# main.net
KiCad netlist of a schematic drawn in EAGLE
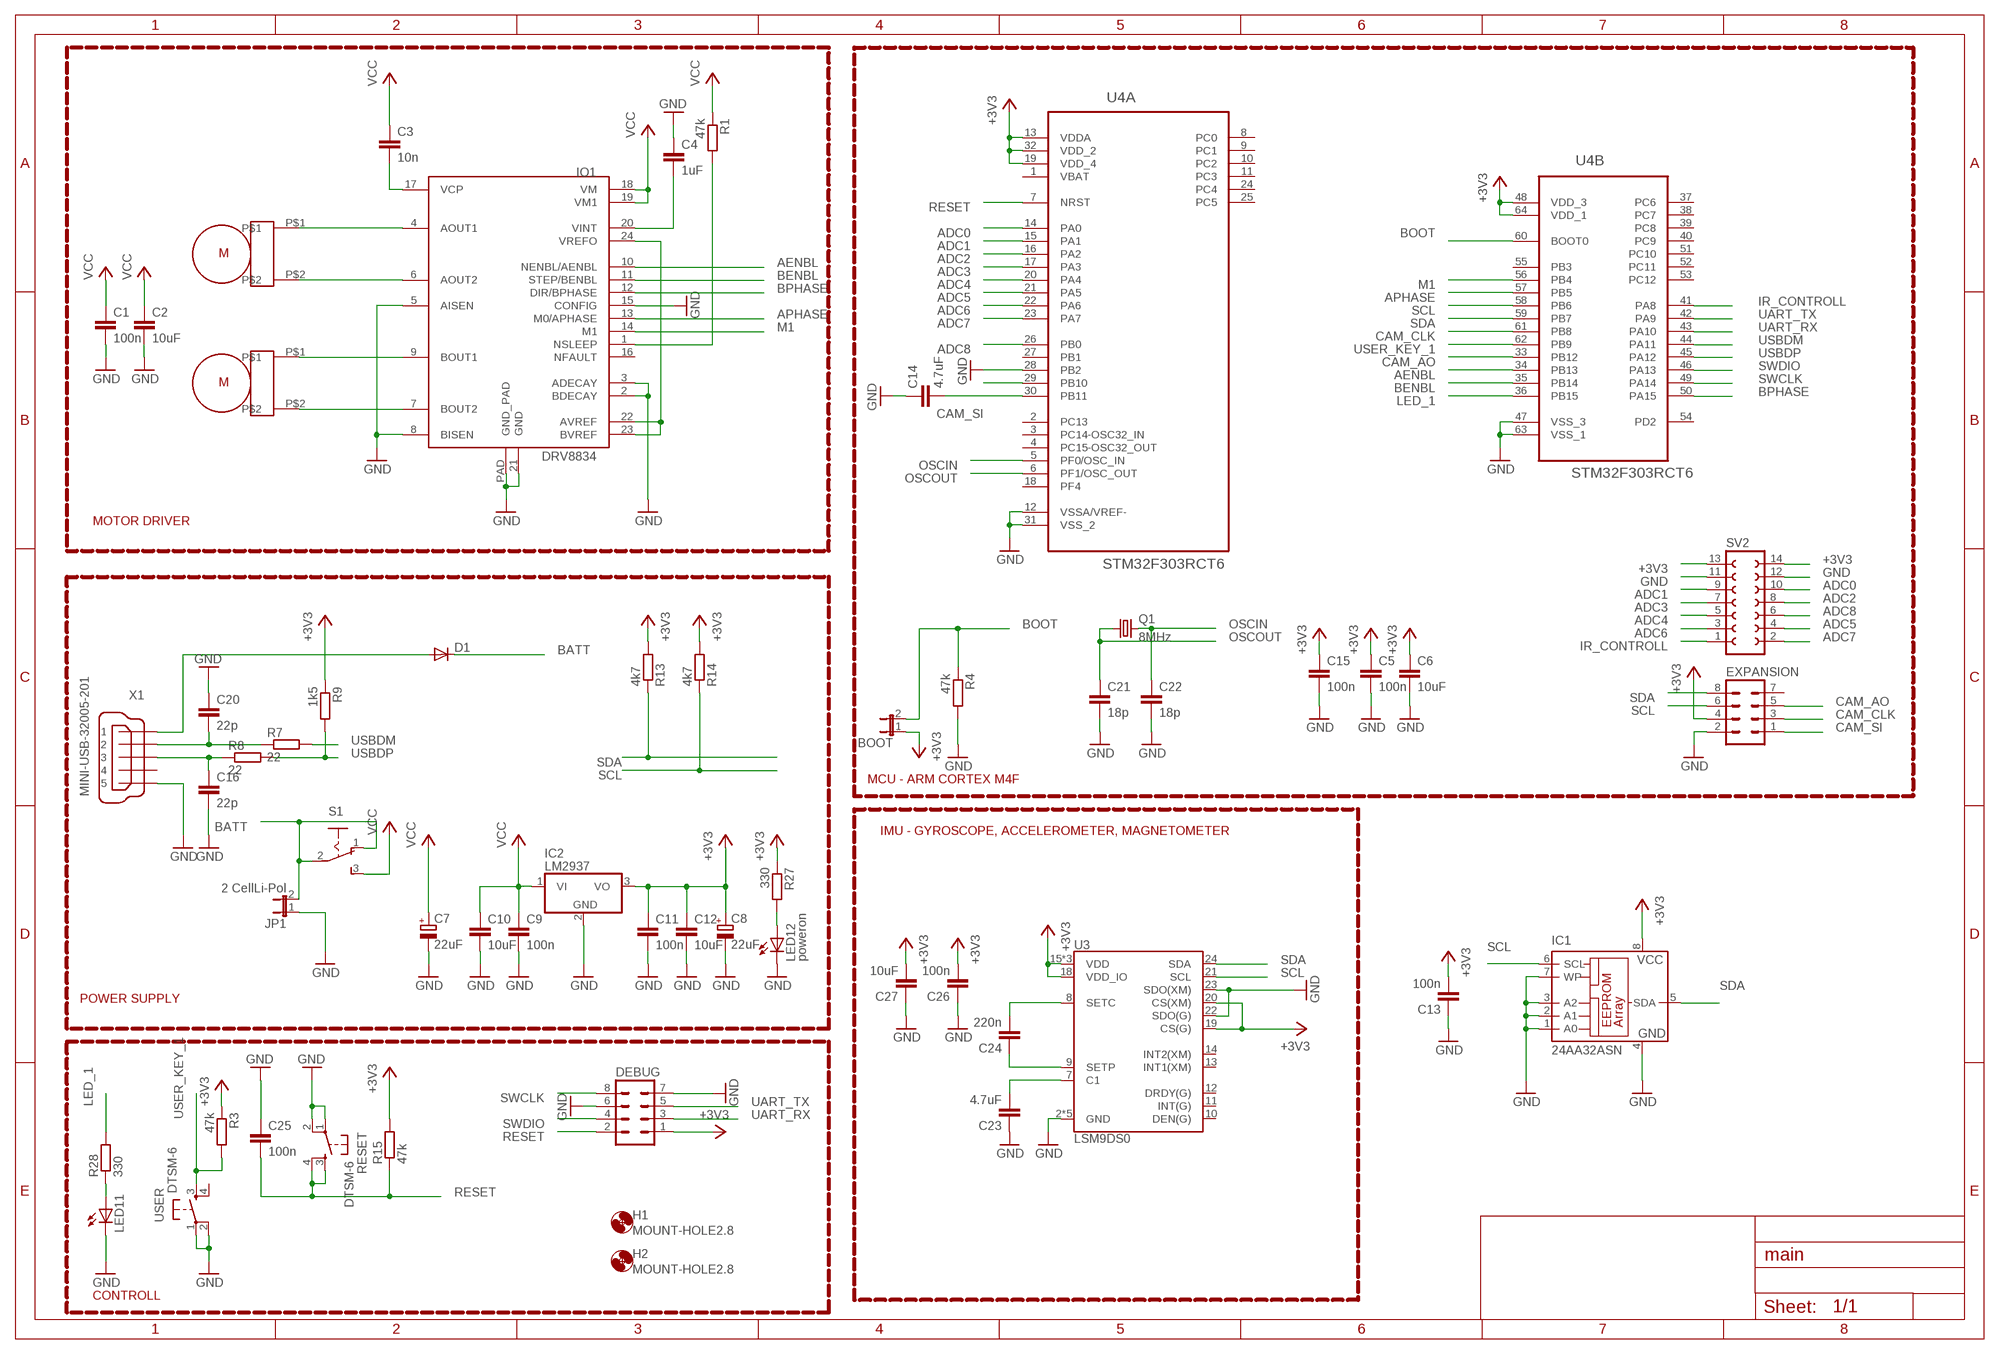
[diagram p0: schematic, sheet 1]

(export (version "E")
  (design (tool "Eeschema 10.0.6"))
  (components
    (comp (ref "BOOT")
      (value "JP1E")
      (footprint "eagle-import:JP1")
      (libsource (lib "eagle-import") (part "JP1E"))
    )
    (comp (ref "C1")
      (value "100n")
      (footprint "eagle-import:C1206")
      (libsource (lib "eagle-import") (part "C-EUC1206"))
    )
    (comp (ref "C2")
      (value "10uF")
      (footprint "eagle-import:C1206")
      (libsource (lib "eagle-import") (part "C-EUC1206"))
    )
    (comp (ref "C3")
      (value "10n")
      (footprint "eagle-import:C1206")
      (libsource (lib "eagle-import") (part "C-EUC1206"))
    )
    (comp (ref "C4")
      (value "1uF")
      (footprint "eagle-import:C1206")
      (libsource (lib "eagle-import") (part "C-EUC1206"))
    )
    (comp (ref "C5")
      (value "100n")
      (footprint "eagle-import:C0805")
      (libsource (lib "eagle-import") (part "C-EUC0805"))
    )
    (comp (ref "C6")
      (value "10uF")
      (footprint "eagle-import:C0805")
      (libsource (lib "eagle-import") (part "C-EUC0805"))
    )
    (comp (ref "C7")
      (value "22uF")
      (footprint "eagle-import:153CLV-0505")
      (libsource (lib "eagle-import") (part "CPOL-EU153CLV-0505"))
    )
    (comp (ref "C8")
      (value "22uF")
      (footprint "eagle-import:153CLV-0505")
      (libsource (lib "eagle-import") (part "CPOL-EU153CLV-0505"))
    )
    (comp (ref "C9")
      (value "100n")
      (footprint "eagle-import:C0805")
      (libsource (lib "eagle-import") (part "C-EUC0805"))
    )
    (comp (ref "C10")
      (value "10uF")
      (footprint "eagle-import:C0805")
      (libsource (lib "eagle-import") (part "C-EUC0805"))
    )
    (comp (ref "C11")
      (value "100n")
      (footprint "eagle-import:C0805")
      (libsource (lib "eagle-import") (part "C-EUC0805"))
    )
    (comp (ref "C12")
      (value "10uF")
      (footprint "eagle-import:C0805")
      (libsource (lib "eagle-import") (part "C-EUC0805"))
    )
    (comp (ref "C13")
      (value "100n")
      (footprint "eagle-import:C0805")
      (libsource (lib "eagle-import") (part "C-EUC0805"))
    )
    (comp (ref "C14")
      (value "4.7uF")
      (footprint "eagle-import:C0805")
      (libsource (lib "eagle-import") (part "C-EUC0805"))
    )
    (comp (ref "C15")
      (value "100n")
      (footprint "eagle-import:C0805")
      (libsource (lib "eagle-import") (part "C-EUC0805"))
    )
    (comp (ref "C16")
      (value "22p")
      (footprint "eagle-import:C0805")
      (libsource (lib "eagle-import") (part "C-EUC0805"))
    )
    (comp (ref "C20")
      (value "22p")
      (footprint "eagle-import:C0805")
      (libsource (lib "eagle-import") (part "C-EUC0805"))
    )
    (comp (ref "C21")
      (value "18p")
      (footprint "eagle-import:C0805")
      (libsource (lib "eagle-import") (part "C-EUC0805"))
    )
    (comp (ref "C22")
      (value "18p")
      (footprint "eagle-import:C0805")
      (libsource (lib "eagle-import") (part "C-EUC0805"))
    )
    (comp (ref "C23")
      (value "4.7uF")
      (footprint "eagle-import:C0805")
      (libsource (lib "eagle-import") (part "C-EUC0805"))
    )
    (comp (ref "C24")
      (value "220n")
      (footprint "eagle-import:C0805")
      (libsource (lib "eagle-import") (part "C-EUC0805"))
    )
    (comp (ref "C25")
      (value "100n")
      (footprint "eagle-import:C0805")
      (libsource (lib "eagle-import") (part "C-EUC0805"))
    )
    (comp (ref "C26")
      (value "100n")
      (footprint "eagle-import:C0805")
      (libsource (lib "eagle-import") (part "C-EUC0805"))
    )
    (comp (ref "C27")
      (value "10uF")
      (footprint "eagle-import:C0805")
      (libsource (lib "eagle-import") (part "C-EUC0805"))
    )
    (comp (ref "D1")
      (value "DIODE-SMB")
      (footprint "eagle-import:SMB")
      (libsource (lib "eagle-import") (part "DIODE-SMB"))
    )
    (comp (ref "DEBUG")
      (value "MA04-2")
      (footprint "eagle-import:MA04-2")
      (libsource (lib "eagle-import") (part "MA04-2"))
    )
    (comp (ref "EXPANSION")
      (value "MA04-2")
      (footprint "eagle-import:MA04-2")
      (libsource (lib "eagle-import") (part "MA04-2"))
    )
    (comp (ref "H1")
      (value "MOUNT-HOLE2.8")
      (footprint "eagle-import:2,8")
      (libsource (lib "eagle-import") (part "MOUNT-HOLE2.8"))
    )
    (comp (ref "H2")
      (value "MOUNT-HOLE2.8")
      (footprint "eagle-import:2,8")
      (libsource (lib "eagle-import") (part "MOUNT-HOLE2.8"))
    )
    (comp (ref "IC1")
      (value "24AA32ASN")
      (footprint "eagle-import:SO-08")
      (fields (field (name "MF") "MICROCHIP") (field (name "MPN") "24AA32A-I/SN"))
      (libsource (lib "eagle-import") (part "24SNAA32A"))
    )
    (comp (ref "IC2")
      (value "LM2937")
      (footprint "eagle-import:TO263-3")
      (libsource (lib "eagle-import") (part "LM2937"))
    )
    (comp (ref "IO1")
      (value "DRV8834")
      (footprint "eagle-import:DRV8834_PCK")
      (libsource (lib "eagle-import") (part "DRV8834"))
    )
    (comp (ref "JP1")
      (value "2 CellLi-Pol")
      (footprint "eagle-import:JP1")
      (libsource (lib "eagle-import") (part "JP1E"))
    )
    (comp (ref "LED11")
      (value "LEDCHIPLED_1206")
      (footprint "eagle-import:CHIPLED_1206")
      (libsource (lib "eagle-import") (part "LEDCHIPLED_1206"))
    )
    (comp (ref "LED12")
      (value "poweron")
      (footprint "eagle-import:CHIPLED_1206")
      (libsource (lib "eagle-import") (part "LEDCHIPLED_1206"))
    )
    (comp (ref "Q1")
      (value "8MHz")
      (footprint "eagle-import:CTS406")
      (libsource (lib "eagle-import") (part "CRYSTALCTS406"))
    )
    (comp (ref "R1")
      (value "47k")
      (footprint "eagle-import:M1206")
      (libsource (lib "eagle-import") (part "R-EU_M1206"))
    )
    (comp (ref "R3")
      (value "47k")
      (footprint "eagle-import:M0805")
      (libsource (lib "eagle-import") (part "R-EU_M0805"))
    )
    (comp (ref "R4")
      (value "47k")
      (footprint "eagle-import:M0805")
      (libsource (lib "eagle-import") (part "R-EU_M0805"))
    )
    (comp (ref "R7")
      (value "22")
      (footprint "eagle-import:M0805")
      (libsource (lib "eagle-import") (part "R-EU_M0805"))
    )
    (comp (ref "R8")
      (value "22")
      (footprint "eagle-import:M0805")
      (libsource (lib "eagle-import") (part "R-EU_M0805"))
    )
    (comp (ref "R9")
      (value "1k5")
      (footprint "eagle-import:M0805")
      (libsource (lib "eagle-import") (part "R-EU_M0805"))
    )
    (comp (ref "R13")
      (value "4k7")
      (footprint "eagle-import:M0805")
      (libsource (lib "eagle-import") (part "R-EU_M0805"))
    )
    (comp (ref "R14")
      (value "4k7")
      (footprint "eagle-import:M0805")
      (libsource (lib "eagle-import") (part "R-EU_M0805"))
    )
    (comp (ref "R15")
      (value "47k")
      (footprint "eagle-import:M0805")
      (libsource (lib "eagle-import") (part "R-EU_M0805"))
    )
    (comp (ref "R27")
      (value "330")
      (footprint "eagle-import:M0805")
      (libsource (lib "eagle-import") (part "R-EU_M0805"))
    )
    (comp (ref "R28")
      (value "330")
      (footprint "eagle-import:M0805")
      (libsource (lib "eagle-import") (part "R-EU_M0805"))
    )
    (comp (ref "RESET")
      (value "DTSM-6")
      (footprint "eagle-import:DTSM-6")
      (libsource (lib "eagle-import") (part "DTSM-6"))
    )
    (comp (ref "S1")
      (value "255SB")
      (footprint "eagle-import:255SB")
      (libsource (lib "eagle-import") (part "255SB"))
    )
    (comp (ref "SV2")
      (value "FE07-2")
      (footprint "eagle-import:FE07-2")
      (libsource (lib "eagle-import") (part "FE07-2"))
    )
    (comp (ref "U$1")
      (value "MICRO_METAL_GEAR_MOTOR")
      (footprint "eagle-import:MICRO_METAL_GEAR_MOTOR")
      (libsource (lib "eagle-import") (part "MICRO_METAL_GEAR_MOTOR"))
    )
    (comp (ref "U$2")
      (value "MICRO_METAL_GEAR_MOTOR")
      (footprint "eagle-import:MICRO_METAL_GEAR_MOTOR")
      (libsource (lib "eagle-import") (part "MICRO_METAL_GEAR_MOTOR"))
    )
    (comp (ref "U3")
      (value "LSM9DS0")
      (footprint "eagle-import:LGA-24")
      (libsource (lib "eagle-import") (part "LSM9DS0"))
    )
    (comp (ref "U4")
      (value "STM32F303RCT6")
      (footprint "eagle-import:QFP50P1200X1200X160-64N")
      (libsource (lib "eagle-import") (part "STM32F303RCT6"))
    )
    (comp (ref "USER")
      (value "DTSM-6")
      (footprint "eagle-import:DTSM-6")
      (libsource (lib "eagle-import") (part "DTSM-6"))
    )
    (comp (ref "X1")
      (value "MINI-USB-32005-201")
      (footprint "eagle-import:32005-201")
      (libsource (lib "eagle-import") (part "MINI-USB-32005-201"))
    )
  )
  (nets
    (net (code "1") (name "+3V3") (class "Default")
      (node (ref "BOOT") (pin "1") (pinfunction "1_1") (pintype "passive"))
      (node (ref "C11") (pin "1") (pinfunction "1_1") (pintype "passive"))
      (node (ref "C12") (pin "1") (pinfunction "1_1") (pintype "passive"))
      (node (ref "C13") (pin "2") (pinfunction "2_2") (pintype "passive"))
      (node (ref "C15") (pin "1") (pinfunction "1_1") (pintype "passive"))
      (node (ref "C26") (pin "2") (pinfunction "2_2") (pintype "passive"))
      (node (ref "C27") (pin "2") (pinfunction "2_2") (pintype "passive"))
      (node (ref "C5") (pin "1") (pinfunction "1_1") (pintype "passive"))
      (node (ref "C6") (pin "1") (pinfunction "1_1") (pintype "passive"))
      (node (ref "C8") (pin "+") (pinfunction "+_+") (pintype "passive"))
      (node (ref "DEBUG") (pin "1") (pinfunction "1_1") (pintype "passive"))
      (node (ref "EXPANSION") (pin "4") (pinfunction "4_4") (pintype "passive"))
      (node (ref "IC1") (pin "8") (pinfunction "VCC_8") (pintype "power_in"))
      (node (ref "IC2") (pin "3") (pinfunction "VO_3") (pintype "passive"))
      (node (ref "R13") (pin "2") (pinfunction "2_2") (pintype "passive"))
      (node (ref "R14") (pin "2") (pinfunction "2_2") (pintype "passive"))
      (node (ref "R15") (pin "2") (pinfunction "2_2") (pintype "passive"))
      (node (ref "R27") (pin "1") (pinfunction "1_1") (pintype "passive"))
      (node (ref "R3") (pin "1") (pinfunction "1_1") (pintype "passive"))
      (node (ref "R9") (pin "1") (pinfunction "1_1") (pintype "passive"))
      (node (ref "SV2") (pin "13") (pinfunction "13_13") (pintype "passive"))
      (node (ref "SV2") (pin "14") (pinfunction "14_14") (pintype "passive"))
      (node (ref "U3") (pin "15") (pinfunction "VDD_15") (pintype "bidirectional"))
      (node (ref "U3") (pin "16") (pinfunction "VDD_16") (pintype "bidirectional"))
      (node (ref "U3") (pin "17") (pinfunction "VDD_17") (pintype "bidirectional"))
      (node (ref "U3") (pin "18") (pinfunction "VDD_IO_18") (pintype "bidirectional"))
      (node (ref "U3") (pin "19") (pinfunction "CS(G)_19") (pintype "bidirectional"))
      (node (ref "U3") (pin "20") (pinfunction "CS(XM)_20") (pintype "bidirectional"))
      (node (ref "U4") (pin "13") (pinfunction "VDDA_13") (pintype "power_in"))
      (node (ref "U4") (pin "19") (pinfunction "VDD_4_19") (pintype "power_in"))
      (node (ref "U4") (pin "32") (pinfunction "VDD_2_32") (pintype "power_in"))
      (node (ref "U4") (pin "48") (pinfunction "VDD_3_48") (pintype "power_in"))
      (node (ref "U4") (pin "64") (pinfunction "VDD_1_64") (pintype "power_in"))
    )
    (net (code "2") (name "/ADC0") (class "Default")
      (node (ref "SV2") (pin "10") (pinfunction "10_10") (pintype "passive"))
      (node (ref "U4") (pin "14") (pinfunction "PA0_14") (pintype "bidirectional"))
    )
    (net (code "3") (name "/ADC1") (class "Default")
      (node (ref "SV2") (pin "9") (pinfunction "9_9") (pintype "passive"))
      (node (ref "U4") (pin "15") (pinfunction "PA1_15") (pintype "bidirectional"))
    )
    (net (code "4") (name "/ADC2") (class "Default")
      (node (ref "SV2") (pin "8") (pinfunction "8_8") (pintype "passive"))
      (node (ref "U4") (pin "16") (pinfunction "PA2_16") (pintype "bidirectional"))
    )
    (net (code "5") (name "/ADC3") (class "Default")
      (node (ref "SV2") (pin "7") (pinfunction "7_7") (pintype "passive"))
      (node (ref "U4") (pin "17") (pinfunction "PA3_17") (pintype "bidirectional"))
    )
    (net (code "6") (name "/ADC4") (class "Default")
      (node (ref "SV2") (pin "5") (pinfunction "5_5") (pintype "passive"))
      (node (ref "U4") (pin "20") (pinfunction "PA4_20") (pintype "bidirectional"))
    )
    (net (code "7") (name "/ADC5") (class "Default")
      (node (ref "SV2") (pin "4") (pinfunction "4_4") (pintype "passive"))
      (node (ref "U4") (pin "21") (pinfunction "PA5_21") (pintype "bidirectional"))
    )
    (net (code "8") (name "/ADC6") (class "Default")
      (node (ref "SV2") (pin "3") (pinfunction "3_3") (pintype "passive"))
      (node (ref "U4") (pin "22") (pinfunction "PA6_22") (pintype "bidirectional"))
    )
    (net (code "9") (name "/ADC7") (class "Default")
      (node (ref "SV2") (pin "2") (pinfunction "2_2") (pintype "passive"))
      (node (ref "U4") (pin "23") (pinfunction "PA7_23") (pintype "bidirectional"))
    )
    (net (code "10") (name "/ADC8") (class "Default")
      (node (ref "SV2") (pin "6") (pinfunction "6_6") (pintype "passive"))
      (node (ref "U4") (pin "26") (pinfunction "PB0_26") (pintype "bidirectional"))
    )
    (net (code "11") (name "/AENBL") (class "Default")
      (node (ref "IO1") (pin "10") (pinfunction "NENBL/AENBL_10") (pintype "bidirectional"))
      (node (ref "U4") (pin "34") (pinfunction "PB13_34") (pintype "bidirectional"))
    )
    (net (code "12") (name "/APHASE") (class "Default")
      (node (ref "IO1") (pin "13") (pinfunction "M0/APHASE_13") (pintype "bidirectional"))
      (node (ref "U4") (pin "57") (pinfunction "PB5_57") (pintype "bidirectional"))
    )
    (net (code "13") (name "/BATT") (class "Default")
      (node (ref "D1") (pin "C") (pinfunction "C_C") (pintype "passive"))
      (node (ref "JP1") (pin "2") (pinfunction "2_2") (pintype "passive"))
      (node (ref "S1") (pin "1") (pinfunction "O_1") (pintype "passive"))
      (node (ref "S1") (pin "2") (pinfunction "P_2") (pintype "passive"))
    )
    (net (code "14") (name "/BENBL") (class "Default")
      (node (ref "IO1") (pin "11") (pinfunction "STEP/BENBL_11") (pintype "bidirectional"))
      (node (ref "U4") (pin "35") (pinfunction "PB14_35") (pintype "bidirectional"))
    )
    (net (code "15") (name "/BOOT") (class "Default")
      (node (ref "BOOT") (pin "2") (pinfunction "2_2") (pintype "passive"))
      (node (ref "R4") (pin "1") (pinfunction "1_1") (pintype "passive"))
      (node (ref "U4") (pin "60") (pinfunction "BOOT0_60") (pintype "input"))
    )
    (net (code "16") (name "/BPHASE") (class "Default")
      (node (ref "IO1") (pin "12") (pinfunction "DIR/BPHASE_12") (pintype "bidirectional"))
      (node (ref "U4") (pin "50") (pinfunction "PA15_50") (pintype "bidirectional"))
    )
    (net (code "17") (name "/CAM_AO") (class "Default")
      (node (ref "EXPANSION") (pin "5") (pinfunction "5_5") (pintype "passive"))
      (node (ref "U4") (pin "33") (pinfunction "PB12_33") (pintype "bidirectional"))
    )
    (net (code "18") (name "/CAM_CLK") (class "Default")
      (node (ref "EXPANSION") (pin "3") (pinfunction "3_3") (pintype "passive"))
      (node (ref "U4") (pin "61") (pinfunction "PB8_61") (pintype "bidirectional"))
    )
    (net (code "19") (name "/CAM_SI") (class "Default")
      (node (ref "EXPANSION") (pin "1") (pinfunction "1_1") (pintype "passive"))
      (node (ref "U4") (pin "29") (pinfunction "PB10_29") (pintype "bidirectional"))
    )
    (net (code "20") (name "/IR_CONTROLL") (class "Default")
      (node (ref "SV2") (pin "1") (pinfunction "1_1") (pintype "passive"))
      (node (ref "U4") (pin "41") (pinfunction "PA8_41") (pintype "bidirectional"))
    )
    (net (code "21") (name "/LED_1") (class "Default")
      (node (ref "R28") (pin "2") (pinfunction "2_2") (pintype "passive"))
      (node (ref "U4") (pin "36") (pinfunction "PB15_36") (pintype "bidirectional"))
    )
    (net (code "22") (name "/M1") (class "Default")
      (node (ref "IO1") (pin "14") (pinfunction "M1_14") (pintype "bidirectional"))
      (node (ref "U4") (pin "56") (pinfunction "PB4_56") (pintype "bidirectional"))
    )
    (net (code "23") (name "/OSCIN") (class "Default")
      (node (ref "C22") (pin "1") (pinfunction "1_1") (pintype "passive"))
      (node (ref "Q1") (pin "3") (pinfunction "2_3") (pintype "passive"))
      (node (ref "U4") (pin "5") (pinfunction "PF0/OSC_IN_5") (pintype "bidirectional"))
    )
    (net (code "24") (name "/OSCOUT") (class "Default")
      (node (ref "C21") (pin "1") (pinfunction "1_1") (pintype "passive"))
      (node (ref "Q1") (pin "1") (pinfunction "1_1") (pintype "passive"))
      (node (ref "U4") (pin "6") (pinfunction "PF1/OSC_OUT_6") (pintype "bidirectional"))
    )
    (net (code "25") (name "/RESET") (class "Default")
      (node (ref "C25") (pin "2") (pinfunction "2_2") (pintype "passive"))
      (node (ref "DEBUG") (pin "2") (pinfunction "2_2") (pintype "passive"))
      (node (ref "R15") (pin "1") (pinfunction "1_1") (pintype "passive"))
      (node (ref "RESET") (pin "3") (pinfunction "3_3") (pintype "passive"))
      (node (ref "RESET") (pin "4") (pinfunction "4_4") (pintype "passive"))
      (node (ref "U4") (pin "7") (pinfunction "NRST_7") (pintype "bidirectional"))
    )
    (net (code "26") (name "/SCL") (class "Default")
      (node (ref "EXPANSION") (pin "6") (pinfunction "6_6") (pintype "passive"))
      (node (ref "IC1") (pin "6") (pinfunction "SCL_6") (pintype "input"))
      (node (ref "R14") (pin "1") (pinfunction "1_1") (pintype "passive"))
      (node (ref "U3") (pin "21") (pinfunction "SCL_21") (pintype "bidirectional"))
      (node (ref "U4") (pin "58") (pinfunction "PB6_58") (pintype "bidirectional"))
    )
    (net (code "27") (name "/SDA") (class "Default")
      (node (ref "EXPANSION") (pin "8") (pinfunction "8_8") (pintype "passive"))
      (node (ref "IC1") (pin "5") (pinfunction "SDA_5") (pintype "bidirectional"))
      (node (ref "R13") (pin "1") (pinfunction "1_1") (pintype "passive"))
      (node (ref "U3") (pin "24") (pinfunction "SDA_24") (pintype "bidirectional"))
      (node (ref "U4") (pin "59") (pinfunction "PB7_59") (pintype "bidirectional"))
    )
    (net (code "28") (name "/SWCLK") (class "Default")
      (node (ref "DEBUG") (pin "8") (pinfunction "8_8") (pintype "passive"))
      (node (ref "U4") (pin "49") (pinfunction "PA14_49") (pintype "bidirectional"))
    )
    (net (code "29") (name "/SWDIO") (class "Default")
      (node (ref "DEBUG") (pin "4") (pinfunction "4_4") (pintype "passive"))
      (node (ref "U4") (pin "46") (pinfunction "PA13_46") (pintype "bidirectional"))
    )
    (net (code "30") (name "/UART_RX") (class "Default")
      (node (ref "DEBUG") (pin "3") (pinfunction "3_3") (pintype "passive"))
      (node (ref "U4") (pin "43") (pinfunction "PA10_43") (pintype "bidirectional"))
    )
    (net (code "31") (name "/UART_TX") (class "Default")
      (node (ref "DEBUG") (pin "5") (pinfunction "5_5") (pintype "passive"))
      (node (ref "U4") (pin "42") (pinfunction "PA9_42") (pintype "bidirectional"))
    )
    (net (code "32") (name "/USBDM") (class "Default")
      (node (ref "R7") (pin "2") (pinfunction "2_2") (pintype "passive"))
      (node (ref "U4") (pin "44") (pinfunction "PA11_44") (pintype "bidirectional"))
    )
    (net (code "33") (name "/USBDP") (class "Default")
      (node (ref "R8") (pin "2") (pinfunction "2_2") (pintype "passive"))
      (node (ref "R9") (pin "2") (pinfunction "2_2") (pintype "passive"))
      (node (ref "U4") (pin "45") (pinfunction "PA12_45") (pintype "bidirectional"))
    )
    (net (code "34") (name "/USER_KEY_1") (class "Default")
      (node (ref "R3") (pin "2") (pinfunction "2_2") (pintype "passive"))
      (node (ref "U4") (pin "62") (pinfunction "PB9_62") (pintype "bidirectional"))
      (node (ref "USER") (pin "3") (pinfunction "3_3") (pintype "passive"))
    )
    (net (code "35") (name "/VBAT") (class "Default")
      (node (ref "U4") (pin "1") (pinfunction "VBAT_1") (pintype "power_in"))
    )
    (net (code "36") (name "GND") (class "Default")
      (node (ref "C1") (pin "2") (pinfunction "2_2") (pintype "passive"))
      (node (ref "C10") (pin "2") (pinfunction "2_2") (pintype "passive"))
      (node (ref "C11") (pin "2") (pinfunction "2_2") (pintype "passive"))
      (node (ref "C12") (pin "2") (pinfunction "2_2") (pintype "passive"))
      (node (ref "C13") (pin "1") (pinfunction "1_1") (pintype "passive"))
      (node (ref "C14") (pin "1") (pinfunction "1_1") (pintype "passive"))
      (node (ref "C15") (pin "2") (pinfunction "2_2") (pintype "passive"))
      (node (ref "C16") (pin "2") (pinfunction "2_2") (pintype "passive"))
      (node (ref "C2") (pin "2") (pinfunction "2_2") (pintype "passive"))
      (node (ref "C20") (pin "1") (pinfunction "1_1") (pintype "passive"))
      (node (ref "C21") (pin "2") (pinfunction "2_2") (pintype "passive"))
      (node (ref "C22") (pin "2") (pinfunction "2_2") (pintype "passive"))
      (node (ref "C23") (pin "1") (pinfunction "1_1") (pintype "passive"))
      (node (ref "C25") (pin "1") (pinfunction "1_1") (pintype "passive"))
      (node (ref "C26") (pin "1") (pinfunction "1_1") (pintype "passive"))
      (node (ref "C27") (pin "1") (pinfunction "1_1") (pintype "passive"))
      (node (ref "C4") (pin "1") (pinfunction "1_1") (pintype "passive"))
      (node (ref "C5") (pin "2") (pinfunction "2_2") (pintype "passive"))
      (node (ref "C6") (pin "2") (pinfunction "2_2") (pintype "passive"))
      (node (ref "C7") (pin "-") (pinfunction "-_-") (pintype "passive"))
      (node (ref "C8") (pin "-") (pinfunction "-_-") (pintype "passive"))
      (node (ref "C9") (pin "2") (pinfunction "2_2") (pintype "passive"))
      (node (ref "DEBUG") (pin "6") (pinfunction "6_6") (pintype "passive"))
      (node (ref "DEBUG") (pin "7") (pinfunction "7_7") (pintype "passive"))
      (node (ref "EXPANSION") (pin "2") (pinfunction "2_2") (pintype "passive"))
      (node (ref "IC1") (pin "1") (pinfunction "A0_1") (pintype "input"))
      (node (ref "IC1") (pin "2") (pinfunction "A1_2") (pintype "input"))
      (node (ref "IC1") (pin "3") (pinfunction "A2_3") (pintype "input"))
      (node (ref "IC1") (pin "4") (pinfunction "GND_4") (pintype "power_in"))
      (node (ref "IC1") (pin "7") (pinfunction "WP_7") (pintype "input"))
      (node (ref "IC2") (pin "2") (pinfunction "GND_2") (pintype "passive"))
      (node (ref "IO1") (pin "15") (pinfunction "CONFIG_15") (pintype "bidirectional"))
      (node (ref "IO1") (pin "2") (pinfunction "BDECAY_2") (pintype "bidirectional"))
      (node (ref "IO1") (pin "21") (pinfunction "GND_21") (pintype "bidirectional"))
      (node (ref "IO1") (pin "3") (pinfunction "ADECAY_3") (pintype "bidirectional"))
      (node (ref "IO1") (pin "5") (pinfunction "AISEN_5") (pintype "bidirectional"))
      (node (ref "IO1") (pin "8") (pinfunction "BISEN_8") (pintype "bidirectional"))
      (node (ref "IO1") (pin "PAD") (pinfunction "GND_PAD_PAD") (pintype "bidirectional"))
      (node (ref "JP1") (pin "1") (pinfunction "1_1") (pintype "passive"))
      (node (ref "LED11") (pin "C") (pinfunction "C_C") (pintype "passive"))
      (node (ref "LED12") (pin "C") (pinfunction "C_C") (pintype "passive"))
      (node (ref "R4") (pin "2") (pinfunction "2_2") (pintype "passive"))
      (node (ref "RESET") (pin "1") (pinfunction "1_1") (pintype "passive"))
      (node (ref "RESET") (pin "2") (pinfunction "2_2") (pintype "passive"))
      (node (ref "SV2") (pin "11") (pinfunction "11_11") (pintype "passive"))
      (node (ref "SV2") (pin "12") (pinfunction "12_12") (pintype "passive"))
      (node (ref "U3") (pin "2") (pinfunction "GND_2") (pintype "bidirectional"))
      (node (ref "U3") (pin "22") (pinfunction "SDO(G)_22") (pintype "bidirectional"))
      (node (ref "U3") (pin "23") (pinfunction "SDO(XM)_23") (pintype "bidirectional"))
      (node (ref "U3") (pin "3") (pinfunction "GND_3") (pintype "bidirectional"))
      (node (ref "U3") (pin "4") (pinfunction "GND_4") (pintype "bidirectional"))
      (node (ref "U3") (pin "5") (pinfunction "GND_5") (pintype "bidirectional"))
      (node (ref "U3") (pin "6") (pinfunction "GND_6") (pintype "bidirectional"))
      (node (ref "U4") (pin "12") (pinfunction "VSSA/VREF-_12") (pintype "power_in"))
      (node (ref "U4") (pin "28") (pinfunction "PB2_28") (pintype "bidirectional"))
      (node (ref "U4") (pin "31") (pinfunction "VSS_2_31") (pintype "passive"))
      (node (ref "U4") (pin "47") (pinfunction "VSS_3_47") (pintype "passive"))
      (node (ref "U4") (pin "63") (pinfunction "VSS_1_63") (pintype "passive"))
      (node (ref "USER") (pin "1") (pinfunction "1_1") (pintype "passive"))
      (node (ref "USER") (pin "2") (pinfunction "2_2") (pintype "passive"))
      (node (ref "X1") (pin "5") (pinfunction "5_5") (pintype "passive"))
    )
    (net (code "37") (name "Net-(C16-Pad1)") (class "Default")
      (node (ref "C16") (pin "1") (pinfunction "1_1") (pintype "passive"))
      (node (ref "R8") (pin "1") (pinfunction "1_1") (pintype "passive"))
      (node (ref "X1") (pin "3") (pinfunction "3_3") (pintype "passive"))
    )
    (net (code "38") (name "Net-(C20-Pad2)") (class "Default")
      (node (ref "C20") (pin "2") (pinfunction "2_2") (pintype "passive"))
      (node (ref "R7") (pin "1") (pinfunction "1_1") (pintype "passive"))
      (node (ref "X1") (pin "2") (pinfunction "2_2") (pintype "passive"))
    )
    (net (code "39") (name "Net-(D1-PadA)") (class "Default")
      (node (ref "D1") (pin "A") (pinfunction "A_A") (pintype "passive"))
      (node (ref "X1") (pin "1") (pinfunction "1_1") (pintype "passive"))
    )
    (net (code "40") (name "Net-(IO1-AOUT1)") (class "Default")
      (node (ref "IO1") (pin "4") (pinfunction "AOUT1_4") (pintype "bidirectional"))
      (node (ref "U$1") (pin "P$1") (pinfunction "P$1_P$1") (pintype "bidirectional"))
    )
    (net (code "41") (name "Net-(IO1-AOUT2)") (class "Default")
      (node (ref "IO1") (pin "6") (pinfunction "AOUT2_6") (pintype "bidirectional"))
      (node (ref "U$1") (pin "P$2") (pinfunction "P$2_P$2") (pintype "bidirectional"))
    )
    (net (code "42") (name "Net-(IO1-AVREF)") (class "Default")
      (node (ref "IO1") (pin "22") (pinfunction "AVREF_22") (pintype "bidirectional"))
      (node (ref "IO1") (pin "23") (pinfunction "BVREF_23") (pintype "bidirectional"))
      (node (ref "IO1") (pin "24") (pinfunction "VREFO_24") (pintype "bidirectional"))
    )
    (net (code "43") (name "Net-(IO1-BOUT1)") (class "Default")
      (node (ref "IO1") (pin "9") (pinfunction "BOUT1_9") (pintype "bidirectional"))
      (node (ref "U$2") (pin "P$1") (pinfunction "P$1_P$1") (pintype "bidirectional"))
    )
    (net (code "44") (name "Net-(IO1-BOUT2)") (class "Default")
      (node (ref "IO1") (pin "7") (pinfunction "BOUT2_7") (pintype "bidirectional"))
      (node (ref "U$2") (pin "P$2") (pinfunction "P$2_P$2") (pintype "bidirectional"))
    )
    (net (code "45") (name "Net-(IO1-NSLEEP)") (class "Default")
      (node (ref "IO1") (pin "1") (pinfunction "NSLEEP_1") (pintype "bidirectional"))
      (node (ref "R1") (pin "2") (pinfunction "2_2") (pintype "passive"))
    )
    (net (code "46") (name "Net-(IO1-VCP)") (class "Default")
      (node (ref "C3") (pin "2") (pinfunction "2_2") (pintype "passive"))
      (node (ref "IO1") (pin "17") (pinfunction "VCP_17") (pintype "bidirectional"))
    )
    (net (code "47") (name "Net-(IO1-VINT)") (class "Default")
      (node (ref "C4") (pin "2") (pinfunction "2_2") (pintype "passive"))
      (node (ref "IO1") (pin "20") (pinfunction "VINT_20") (pintype "bidirectional"))
    )
    (net (code "48") (name "Net-(LED11-PadA)") (class "Default")
      (node (ref "LED11") (pin "A") (pinfunction "A_A") (pintype "passive"))
      (node (ref "R28") (pin "1") (pinfunction "1_1") (pintype "passive"))
    )
    (net (code "49") (name "Net-(LED12-PadA)") (class "Default")
      (node (ref "LED12") (pin "A") (pinfunction "A_A") (pintype "passive"))
      (node (ref "R27") (pin "2") (pinfunction "2_2") (pintype "passive"))
    )
    (net (code "50") (name "Net-(U3-C1)") (class "Default")
      (node (ref "C23") (pin "2") (pinfunction "2_2") (pintype "passive"))
      (node (ref "U3") (pin "7") (pinfunction "C1_7") (pintype "bidirectional"))
    )
    (net (code "51") (name "Net-(U3-SETC)") (class "Default")
      (node (ref "C24") (pin "2") (pinfunction "2_2") (pintype "passive"))
      (node (ref "U3") (pin "8") (pinfunction "SETC_8") (pintype "bidirectional"))
    )
    (net (code "52") (name "Net-(U3-SETP)") (class "Default")
      (node (ref "C24") (pin "1") (pinfunction "1_1") (pintype "passive"))
      (node (ref "U3") (pin "9") (pinfunction "SETP_9") (pintype "bidirectional"))
    )
    (net (code "53") (name "Net-(U4A-PB11)") (class "Default")
      (node (ref "C14") (pin "2") (pinfunction "2_2") (pintype "passive"))
      (node (ref "U4") (pin "30") (pinfunction "PB11_30") (pintype "bidirectional"))
    )
    (net (code "54") (name "VCC") (class "Default")
      (node (ref "C1") (pin "1") (pinfunction "1_1") (pintype "passive"))
      (node (ref "C10") (pin "1") (pinfunction "1_1") (pintype "passive"))
      (node (ref "C2") (pin "1") (pinfunction "1_1") (pintype "passive"))
      (node (ref "C3") (pin "1") (pinfunction "1_1") (pintype "passive"))
      (node (ref "C7") (pin "+") (pinfunction "+_+") (pintype "passive"))
      (node (ref "C9") (pin "1") (pinfunction "1_1") (pintype "passive"))
      (node (ref "IC2") (pin "1") (pinfunction "VI_1") (pintype "input"))
      (node (ref "IO1") (pin "18") (pinfunction "VM_18") (pintype "bidirectional"))
      (node (ref "IO1") (pin "19") (pinfunction "VM1_19") (pintype "bidirectional"))
      (node (ref "R1") (pin "1") (pinfunction "1_1") (pintype "passive"))
      (node (ref "S1") (pin "3") (pinfunction "S_3") (pintype "passive"))
    )
    (net (code "55") (name "unconnected-(EXPANSION-Pad7)") (class "Default")
      (node (ref "EXPANSION") (pin "7") (pinfunction "7_7") (pintype "passive"))
    )
    (net (code "56") (name "unconnected-(IO1-NFAULT-Pad16)") (class "Default")
      (node (ref "IO1") (pin "16") (pinfunction "NFAULT_16") (pintype "bidirectional"))
    )
    (net (code "57") (name "unconnected-(U3-DEN(G)-Pad10)") (class "Default")
      (node (ref "U3") (pin "10") (pinfunction "DEN(G)_10") (pintype "bidirectional"))
    )
    (net (code "58") (name "unconnected-(U3-DRDY(G)-Pad12)") (class "Default")
      (node (ref "U3") (pin "12") (pinfunction "DRDY(G)_12") (pintype "bidirectional"))
    )
    (net (code "59") (name "unconnected-(U3-INT(G)-Pad11)") (class "Default")
      (node (ref "U3") (pin "11") (pinfunction "INT(G)_11") (pintype "bidirectional"))
    )
    (net (code "60") (name "unconnected-(U3-INT1(XM)-Pad13)") (class "Default")
      (node (ref "U3") (pin "13") (pinfunction "INT1(XM)_13") (pintype "bidirectional"))
    )
    (net (code "61") (name "unconnected-(U3-INT2(XM)-Pad14)") (class "Default")
      (node (ref "U3") (pin "14") (pinfunction "INT2(XM)_14") (pintype "bidirectional"))
    )
    (net (code "62") (name "unconnected-(U4A-PB1-Pad27)") (class "Default")
      (node (ref "U4") (pin "27") (pinfunction "PB1_27") (pintype "bidirectional"))
    )
    (net (code "63") (name "unconnected-(U4A-PC0-Pad8)") (class "Default")
      (node (ref "U4") (pin "8") (pinfunction "PC0_8") (pintype "bidirectional"))
    )
    (net (code "64") (name "unconnected-(U4A-PC1-Pad9)") (class "Default")
      (node (ref "U4") (pin "9") (pinfunction "PC1_9") (pintype "bidirectional"))
    )
    (net (code "65") (name "unconnected-(U4A-PC2-Pad10)") (class "Default")
      (node (ref "U4") (pin "10") (pinfunction "PC2_10") (pintype "bidirectional"))
    )
    (net (code "66") (name "unconnected-(U4A-PC3-Pad11)") (class "Default")
      (node (ref "U4") (pin "11") (pinfunction "PC3_11") (pintype "bidirectional"))
    )
    (net (code "67") (name "unconnected-(U4A-PC4-Pad24)") (class "Default")
      (node (ref "U4") (pin "24") (pinfunction "PC4_24") (pintype "bidirectional"))
    )
    (net (code "68") (name "unconnected-(U4A-PC5-Pad25)") (class "Default")
      (node (ref "U4") (pin "25") (pinfunction "PC5_25") (pintype "bidirectional"))
    )
    (net (code "69") (name "unconnected-(U4A-PC13-Pad2)") (class "Default")
      (node (ref "U4") (pin "2") (pinfunction "PC13_2") (pintype "bidirectional"))
    )
    (net (code "70") (name "unconnected-(U4A-PC14-OSC32_IN-Pad3)") (class "Default")
      (node (ref "U4") (pin "3") (pinfunction "PC14-OSC32_IN_3") (pintype "bidirectional"))
    )
    (net (code "71") (name "unconnected-(U4A-PC15-OSC32_OUT-Pad4)") (class "Default")
      (node (ref "U4") (pin "4") (pinfunction "PC15-OSC32_OUT_4") (pintype "bidirectional"))
    )
    (net (code "72") (name "unconnected-(U4A-PF4-Pad18)") (class "Default")
      (node (ref "U4") (pin "18") (pinfunction "PF4_18") (pintype "bidirectional"))
    )
    (net (code "73") (name "unconnected-(U4B-PB3-Pad55)") (class "Default")
      (node (ref "U4") (pin "55") (pinfunction "PB3_55") (pintype "bidirectional"))
    )
    (net (code "74") (name "unconnected-(U4B-PC6-Pad37)") (class "Default")
      (node (ref "U4") (pin "37") (pinfunction "PC6_37") (pintype "bidirectional"))
    )
    (net (code "75") (name "unconnected-(U4B-PC7-Pad38)") (class "Default")
      (node (ref "U4") (pin "38") (pinfunction "PC7_38") (pintype "bidirectional"))
    )
    (net (code "76") (name "unconnected-(U4B-PC8-Pad39)") (class "Default")
      (node (ref "U4") (pin "39") (pinfunction "PC8_39") (pintype "bidirectional"))
    )
    (net (code "77") (name "unconnected-(U4B-PC9-Pad40)") (class "Default")
      (node (ref "U4") (pin "40") (pinfunction "PC9_40") (pintype "bidirectional"))
    )
    (net (code "78") (name "unconnected-(U4B-PC10-Pad51)") (class "Default")
      (node (ref "U4") (pin "51") (pinfunction "PC10_51") (pintype "bidirectional"))
    )
    (net (code "79") (name "unconnected-(U4B-PC11-Pad52)") (class "Default")
      (node (ref "U4") (pin "52") (pinfunction "PC11_52") (pintype "bidirectional"))
    )
    (net (code "80") (name "unconnected-(U4B-PC12-Pad53)") (class "Default")
      (node (ref "U4") (pin "53") (pinfunction "PC12_53") (pintype "bidirectional"))
    )
    (net (code "81") (name "unconnected-(U4B-PD2-Pad54)") (class "Default")
      (node (ref "U4") (pin "54") (pinfunction "PD2_54") (pintype "bidirectional"))
    )
    (net (code "82") (name "unconnected-(USER-Pad4)") (class "Default")
      (node (ref "USER") (pin "4") (pinfunction "4_4") (pintype "passive"))
    )
    (net (code "83") (name "unconnected-(X1-Pad4)") (class "Default")
      (node (ref "X1") (pin "4") (pinfunction "4_4") (pintype "passive"))
    )
  )
)
